# HH-08MX.net
KiCad netlist of a schematic drawn in EAGLE
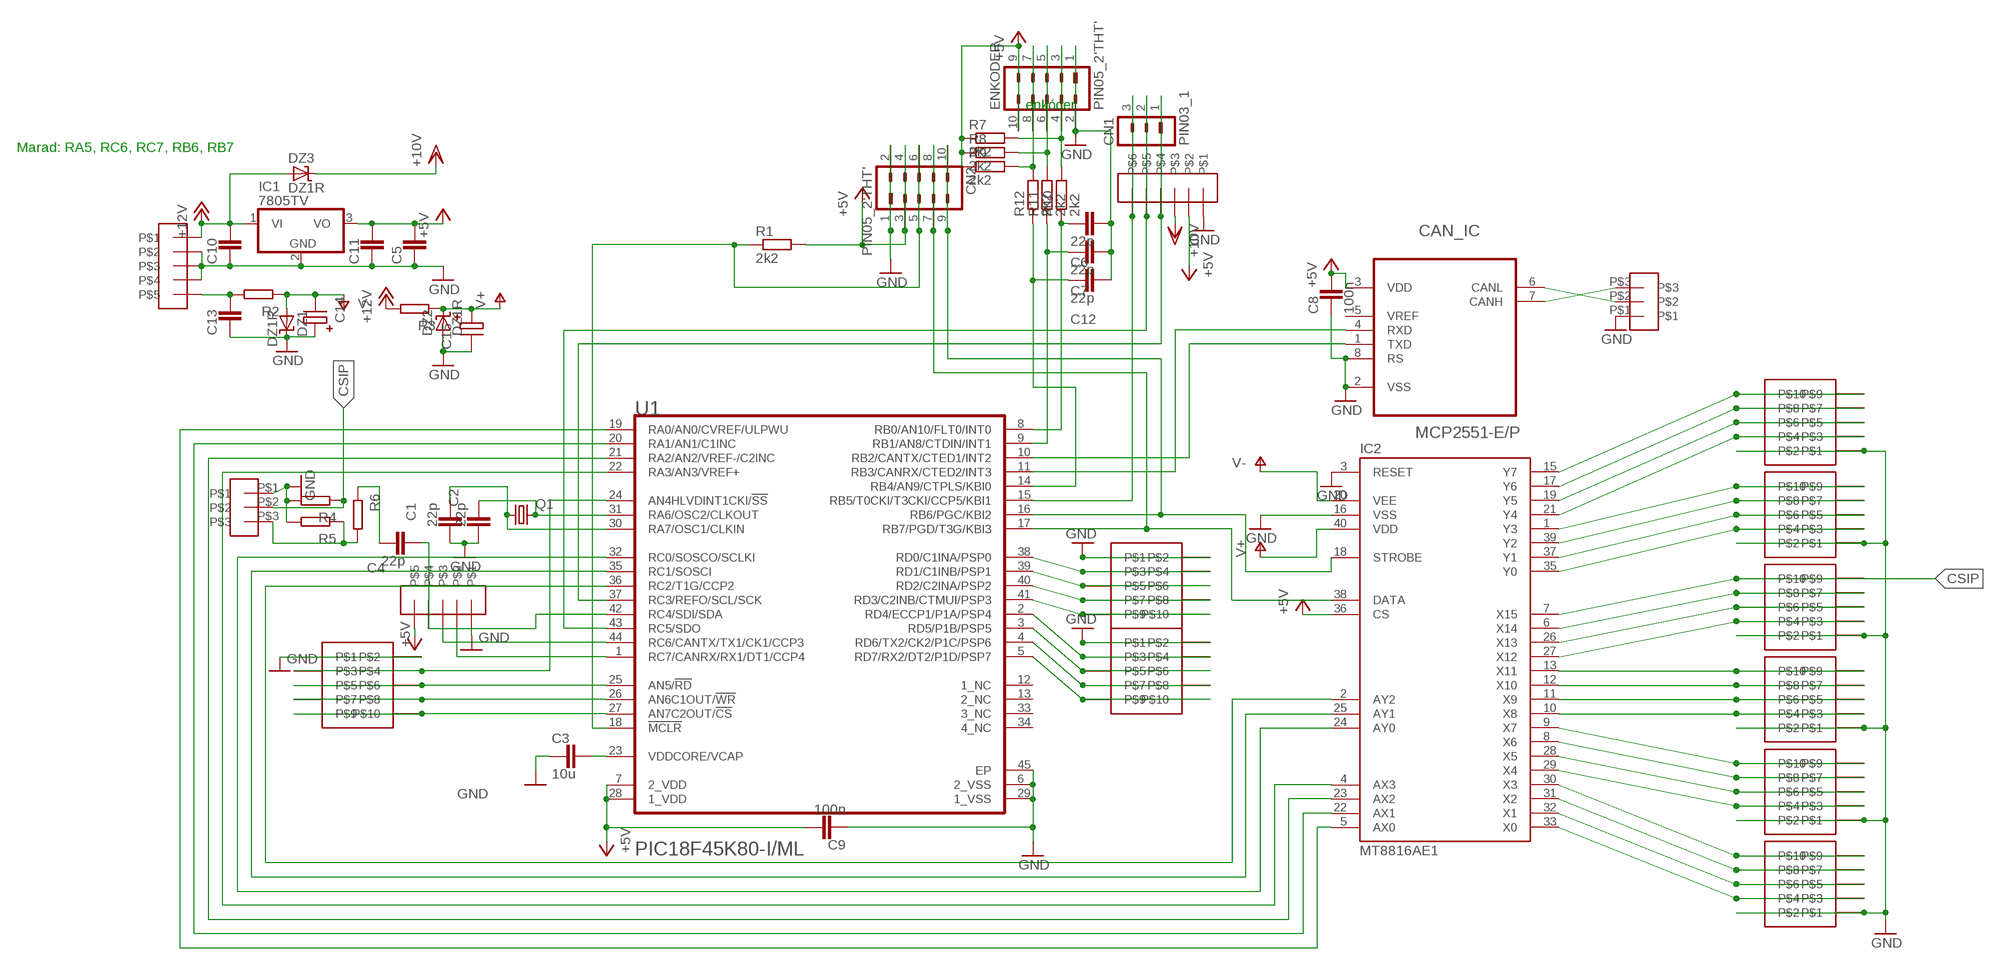
[diagram p0: schematic, sheet 1]

(export (version "E")
  (design (tool "Eeschema 10.0.6"))
  (components
    (comp (ref "BE1-4")
      (value "KERETES_TUS_10")
      (footprint "eagle-import:KERETES_TUS_10")
      (libsource (lib "eagle-import") (part "KERETES_TUS_10"))
    )
    (comp (ref "BE5-8")
      (value "KERETES_TUS_10")
      (footprint "eagle-import:KERETES_TUS_10")
      (libsource (lib "eagle-import") (part "KERETES_TUS_10"))
    )
    (comp (ref "BE9-12")
      (value "KERETES_TUS_10")
      (footprint "eagle-import:KERETES_TUS_10")
      (libsource (lib "eagle-import") (part "KERETES_TUS_10"))
    )
    (comp (ref "BE13-16")
      (value "KERETES_TUS_10")
      (footprint "eagle-import:KERETES_TUS_10")
      (libsource (lib "eagle-import") (part "KERETES_TUS_10"))
    )
    (comp (ref "C1")
      (value "22p")
      (footprint "eagle-import:R_0805_NAGY")
      (libsource (lib "eagle-import") (part "C0805_NAGY"))
    )
    (comp (ref "C2")
      (value "22p")
      (footprint "eagle-import:R_0805_NAGY")
      (libsource (lib "eagle-import") (part "C0805_NAGY"))
    )
    (comp (ref "C3")
      (value "10u")
      (footprint "eagle-import:R_0805_NAGY")
      (libsource (lib "eagle-import") (part "C0805_NAGY"))
    )
    (comp (ref "C4")
      (value "22p")
      (footprint "eagle-import:R_0805_NAGY")
      (libsource (lib "eagle-import") (part "C0805_NAGY"))
    )
    (comp (ref "C5")
      (value "C0805_NAGY")
      (footprint "eagle-import:R_0805_NAGY")
      (libsource (lib "eagle-import") (part "C0805_NAGY"))
    )
    (comp (ref "C6")
      (value "22p")
      (footprint "eagle-import:R_0805_NAGY")
      (libsource (lib "eagle-import") (part "C0805_NAGY"))
    )
    (comp (ref "C7")
      (value "22p")
      (footprint "eagle-import:R_0805_NAGY")
      (libsource (lib "eagle-import") (part "C0805_NAGY"))
    )
    (comp (ref "C8")
      (value "100n")
      (footprint "eagle-import:R_0805_NAGY")
      (libsource (lib "eagle-import") (part "C0805_NAGY"))
    )
    (comp (ref "C9")
      (value "100n")
      (footprint "eagle-import:R_0805_NAGY")
      (libsource (lib "eagle-import") (part "C0805_NAGY"))
    )
    (comp (ref "C10")
      (value "C0805_NAGY")
      (footprint "eagle-import:R_0805_NAGY")
      (libsource (lib "eagle-import") (part "C0805_NAGY"))
    )
    (comp (ref "C11")
      (value "C0805_NAGY")
      (footprint "eagle-import:R_0805_NAGY")
      (libsource (lib "eagle-import") (part "C0805_NAGY"))
    )
    (comp (ref "C12")
      (value "22p")
      (footprint "eagle-import:R_0805_NAGY")
      (libsource (lib "eagle-import") (part "C0805_NAGY"))
    )
    (comp (ref "C13")
      (value "C0805_NAGY")
      (footprint "eagle-import:R_0805_NAGY")
      (libsource (lib "eagle-import") (part "C0805_NAGY"))
    )
    (comp (ref "C14")
      (value "C_EL1R06")
      (footprint "eagle-import:C_EL1RASZT06")
      (libsource (lib "eagle-import") (part "C_EL1R06"))
    )
    (comp (ref "C15")
      (value "C_EL1R06")
      (footprint "eagle-import:C_EL1RASZT06")
      (libsource (lib "eagle-import") (part "C_EL1R06"))
    )
    (comp (ref "CAN_IC")
      (value "MCP2551-E/P")
      (footprint "eagle-import:DIP254P762X432-8")
      (libsource (lib "eagle-import") (part "MCP2551-E/P"))
    )
    (comp (ref "CN1")
      (value "PIN03_1")
      (footprint "eagle-import:PIN03_1")
      (libsource (lib "eagle-import") (part "PIN03_1"))
    )
    (comp (ref "CN2")
      (value "PIN05_2'THT'")
      (footprint "eagle-import:PIN05_2")
      (libsource (lib "eagle-import") (part "PIN05_2'THT'"))
    )
    (comp (ref "DZ1")
      (value "DZ1R")
      (footprint "eagle-import:D1RASZT")
      (libsource (lib "eagle-import") (part "DZ1R"))
    )
    (comp (ref "DZ2")
      (value "DZ1R")
      (footprint "eagle-import:D1RASZT")
      (libsource (lib "eagle-import") (part "DZ1R"))
    )
    (comp (ref "DZ3")
      (value "DZ1R")
      (footprint "eagle-import:D1RASZT")
      (libsource (lib "eagle-import") (part "DZ1R"))
    )
    (comp (ref "ENKODER")
      (value "PIN05_2'THT'")
      (footprint "eagle-import:PIN05_2")
      (libsource (lib "eagle-import") (part "PIN05_2'THT'"))
    )
    (comp (ref "IC1")
      (value "7805TV")
      (footprint "eagle-import:TO220V")
      (libsource (lib "eagle-import") (part "78TV05"))
    )
    (comp (ref "IC2")
      (value "MT8816AE1")
      (footprint "eagle-import:DIL40")
      (libsource (lib "eagle-import") (part "MT8816AE1"))
    )
    (comp (ref "KI1-4")
      (value "KERETES_TUS_10")
      (footprint "eagle-import:KERETES_TUS_10")
      (libsource (lib "eagle-import") (part "KERETES_TUS_10"))
    )
    (comp (ref "KI5-8")
      (value "KERETES_TUS_10")
      (footprint "eagle-import:KERETES_TUS_10")
      (libsource (lib "eagle-import") (part "KERETES_TUS_10"))
    )
    (comp (ref "KIJELZO")
      (value "FEHER_TUS_6")
      (footprint "eagle-import:FEHER_TUS_6")
      (libsource (lib "eagle-import") (part "FEHER_TUS_6"))
    )
    (comp (ref "Q1")
      (value "XTAL_2QS")
      (footprint "eagle-import:XTAL_QS")
      (libsource (lib "eagle-import") (part "XTAL_2QS"))
    )
    (comp (ref "R1")
      (value "2k2")
      (footprint "eagle-import:R0805")
      (libsource (lib "eagle-import") (part "R-EU_R0805"))
    )
    (comp (ref "R2")
      (value "R_EU0805_NAGY")
      (footprint "eagle-import:R_0805_NAGY")
      (libsource (lib "eagle-import") (part "R_EU0805_NAGY"))
    )
    (comp (ref "R3")
      (value "R_EU0805_NAGY")
      (footprint "eagle-import:R_0805_NAGY")
      (libsource (lib "eagle-import") (part "R_EU0805_NAGY"))
    )
    (comp (ref "R4")
      (value "R_EU0805_NAGY")
      (footprint "eagle-import:R_0805_NAGY")
      (libsource (lib "eagle-import") (part "R_EU0805_NAGY"))
    )
    (comp (ref "R5")
      (value "R_EU0805_NAGY")
      (footprint "eagle-import:R_0805_NAGY")
      (libsource (lib "eagle-import") (part "R_EU0805_NAGY"))
    )
    (comp (ref "R6")
      (value "R_EU0805_NAGY")
      (footprint "eagle-import:R_0805_NAGY")
      (libsource (lib "eagle-import") (part "R_EU0805_NAGY"))
    )
    (comp (ref "R7")
      (value "2k2")
      (footprint "eagle-import:R0805")
      (libsource (lib "eagle-import") (part "R-EU_R0805"))
    )
    (comp (ref "R8")
      (value "2k2")
      (footprint "eagle-import:R0805")
      (libsource (lib "eagle-import") (part "R-EU_R0805"))
    )
    (comp (ref "R9")
      (value "2k2")
      (footprint "eagle-import:R0805")
      (libsource (lib "eagle-import") (part "R-EU_R0805"))
    )
    (comp (ref "R10")
      (value "2k2")
      (footprint "eagle-import:R0805")
      (libsource (lib "eagle-import") (part "R-EU_R0805"))
    )
    (comp (ref "R11")
      (value "2k2")
      (footprint "eagle-import:R0805")
      (libsource (lib "eagle-import") (part "R-EU_R0805"))
    )
    (comp (ref "R12")
      (value "2k2")
      (footprint "eagle-import:R0805")
      (libsource (lib "eagle-import") (part "R-EU_R0805"))
    )
    (comp (ref "SOROSPORT")
      (value "FEHER_TUS_5")
      (footprint "eagle-import:FEHER_TUS_5")
      (libsource (lib "eagle-import") (part "FEHER_TUS_5"))
    )
    (comp (ref "U$1")
      (value "FEHER_TUS_3")
      (footprint "eagle-import:FEHER_TUS_3")
      (libsource (lib "eagle-import") (part "FEHER_TUS_3"))
    )
    (comp (ref "U$4")
      (value "FEHER_TUS_3")
      (footprint "eagle-import:FEHER_TUS_3")
      (libsource (lib "eagle-import") (part "FEHER_TUS_3"))
    )
    (comp (ref "U$5")
      (value "FEHER_TUS_5")
      (footprint "eagle-import:FEHER_TUS_5")
      (libsource (lib "eagle-import") (part "FEHER_TUS_5"))
    )
    (comp (ref "U$14")
      (value "KERETES_TUS_10")
      (footprint "eagle-import:KERETES_TUS_10")
      (libsource (lib "eagle-import") (part "KERETES_TUS_10"))
    )
    (comp (ref "U$15")
      (value "KERETES_TUS_10")
      (footprint "eagle-import:KERETES_TUS_10")
      (libsource (lib "eagle-import") (part "KERETES_TUS_10"))
    )
    (comp (ref "U$16")
      (value "KERETES_TUS_10")
      (footprint "eagle-import:KERETES_TUS_10")
      (libsource (lib "eagle-import") (part "KERETES_TUS_10"))
    )
    (comp (ref "U1")
      (value "MICROCHIP_PIC18F45K80-I-MLMICROCHIP_PIC18F45K80-I-ML_0_2")
      (footprint "eagle-import:MICROCHIP_PIC18F45K80-I-ML_2")
      (fields (field (name "MF") "Microchip") (field (name "MPN") "PIC18F45K80-I/ML"))
      (libsource (lib "eagle-import") (part "MICROCHIP_PIC18F45K80-I-MLMICROCHIP_PIC18F45K80-I-ML_0_2"))
    )
  )
  (nets
    (net (code "1") (name "+5V") (class "Default")
      (node (ref "C11") (pin "1") (pinfunction "1_1") (pintype "passive"))
      (node (ref "C5") (pin "1") (pinfunction "1_1") (pintype "passive"))
      (node (ref "C8") (pin "1") (pinfunction "1_1") (pintype "passive"))
      (node (ref "C9") (pin "1") (pinfunction "1_1") (pintype "passive"))
      (node (ref "CAN_IC") (pin "3") (pinfunction "VDD_3") (pintype "power_in"))
      (node (ref "CN2") (pin "3") (pinfunction "3_3") (pintype "passive"))
      (node (ref "CN2") (pin "4") (pinfunction "4_4") (pintype "passive"))
      (node (ref "ENKODER") (pin "10") (pinfunction "10_10") (pintype "passive"))
      (node (ref "ENKODER") (pin "9") (pinfunction "9_9") (pintype "passive"))
      (node (ref "IC1") (pin "3") (pinfunction "VO_3") (pintype "passive"))
      (node (ref "IC2") (pin "36") (pinfunction "CS_36") (pintype "input"))
      (node (ref "KIJELZO") (pin "P$2") (pinfunction "P$2_P$2") (pintype "bidirectional"))
      (node (ref "R1") (pin "2") (pinfunction "2_2") (pintype "passive"))
      (node (ref "R7") (pin "1") (pinfunction "1_1") (pintype "passive"))
      (node (ref "R8") (pin "1") (pinfunction "1_1") (pintype "passive"))
      (node (ref "R9") (pin "1") (pinfunction "1_1") (pintype "passive"))
      (node (ref "SOROSPORT") (pin "P$5") (pinfunction "P$5_P$5") (pintype "bidirectional"))
      (node (ref "U1") (pin "28") (pinfunction "1_VDD_28") (pintype "power_in"))
      (node (ref "U1") (pin "7") (pinfunction "2_VDD_7") (pintype "power_in"))
    )
    (net (code "2") (name "+10V") (class "Default")
      (node (ref "DZ3") (pin "P$2") (pinfunction "C_P$2") (pintype "passive"))
      (node (ref "KIJELZO") (pin "P$3") (pinfunction "P$3_P$3") (pintype "bidirectional"))
    )
    (net (code "3") (name "+12V") (class "Default")
      (node (ref "C10") (pin "1") (pinfunction "1_1") (pintype "passive"))
      (node (ref "DZ3") (pin "P$1") (pinfunction "A_P$1") (pintype "passive"))
      (node (ref "IC1") (pin "1") (pinfunction "VI_1") (pintype "input"))
      (node (ref "R3") (pin "2") (pinfunction "E_2") (pintype "passive"))
      (node (ref "U$5") (pin "P$1") (pinfunction "P$1_P$1") (pintype "bidirectional"))
    )
    (net (code "4") (name "CSIP") (class "Default")
      (node (ref "BE13-16") (pin "P$10") (pinfunction "P$10_P$10") (pintype "bidirectional"))
      (node (ref "BE13-16") (pin "P$9") (pinfunction "P$9_P$9") (pintype "bidirectional"))
      (node (ref "IC2") (pin "7") (pinfunction "X15_7") (pintype "bidirectional"))
      (node (ref "R4") (pin "1") (pinfunction "A_1") (pintype "passive"))
      (node (ref "U$1") (pin "P$2") (pinfunction "P$2_P$2") (pintype "bidirectional"))
    )
    (net (code "5") (name "GND") (class "Default")
      (node (ref "BE1-4") (pin "P$1") (pinfunction "P$1_P$1") (pintype "bidirectional"))
      (node (ref "BE1-4") (pin "P$2") (pinfunction "P$2_P$2") (pintype "bidirectional"))
      (node (ref "BE13-16") (pin "P$1") (pinfunction "P$1_P$1") (pintype "bidirectional"))
      (node (ref "BE13-16") (pin "P$2") (pinfunction "P$2_P$2") (pintype "bidirectional"))
      (node (ref "BE5-8") (pin "P$1") (pinfunction "P$1_P$1") (pintype "bidirectional"))
      (node (ref "BE5-8") (pin "P$2") (pinfunction "P$2_P$2") (pintype "bidirectional"))
      (node (ref "BE9-12") (pin "P$1") (pinfunction "P$1_P$1") (pintype "bidirectional"))
      (node (ref "BE9-12") (pin "P$2") (pinfunction "P$2_P$2") (pintype "bidirectional"))
      (node (ref "C1") (pin "1") (pinfunction "1_1") (pintype "passive"))
      (node (ref "C10") (pin "2") (pinfunction "2_2") (pintype "passive"))
      (node (ref "C11") (pin "2") (pinfunction "2_2") (pintype "passive"))
      (node (ref "C12") (pin "1") (pinfunction "1_1") (pintype "passive"))
      (node (ref "C13") (pin "2") (pinfunction "2_2") (pintype "passive"))
      (node (ref "C14") (pin "P+") (pinfunction "P+_P+") (pintype "passive"))
      (node (ref "C15") (pin "P-") (pinfunction "P-_P-") (pintype "passive"))
      (node (ref "C2") (pin "1") (pinfunction "1_1") (pintype "passive"))
      (node (ref "C3") (pin "2") (pinfunction "2_2") (pintype "passive"))
      (node (ref "C5") (pin "2") (pinfunction "2_2") (pintype "passive"))
      (node (ref "C6") (pin "1") (pinfunction "1_1") (pintype "passive"))
      (node (ref "C7") (pin "1") (pinfunction "1_1") (pintype "passive"))
      (node (ref "C8") (pin "2") (pinfunction "2_2") (pintype "passive"))
      (node (ref "C9") (pin "2") (pinfunction "2_2") (pintype "passive"))
      (node (ref "CAN_IC") (pin "2") (pinfunction "VSS_2") (pintype "passive"))
      (node (ref "CAN_IC") (pin "8") (pinfunction "RS_8") (pintype "input"))
      (node (ref "CN2") (pin "1") (pinfunction "1_1") (pintype "passive"))
      (node (ref "CN2") (pin "2") (pinfunction "2_2") (pintype "passive"))
      (node (ref "DZ1") (pin "P$2") (pinfunction "C_P$2") (pintype "passive"))
      (node (ref "DZ2") (pin "P$1") (pinfunction "A_P$1") (pintype "passive"))
      (node (ref "ENKODER") (pin "1") (pinfunction "1_1") (pintype "passive"))
      (node (ref "ENKODER") (pin "2") (pinfunction "2_2") (pintype "passive"))
      (node (ref "IC1") (pin "2") (pinfunction "GND_2") (pintype "passive"))
      (node (ref "IC2") (pin "16") (pinfunction "VSS_16") (pintype "power_in"))
      (node (ref "IC2") (pin "3") (pinfunction "RESET_3") (pintype "input"))
      (node (ref "KI1-4") (pin "P$1") (pinfunction "P$1_P$1") (pintype "bidirectional"))
      (node (ref "KI1-4") (pin "P$2") (pinfunction "P$2_P$2") (pintype "bidirectional"))
      (node (ref "KI5-8") (pin "P$1") (pinfunction "P$1_P$1") (pintype "bidirectional"))
      (node (ref "KI5-8") (pin "P$2") (pinfunction "P$2_P$2") (pintype "bidirectional"))
      (node (ref "KIJELZO") (pin "P$1") (pinfunction "P$1_P$1") (pintype "bidirectional"))
      (node (ref "R4") (pin "2") (pinfunction "E_2") (pintype "passive"))
      (node (ref "R5") (pin "2") (pinfunction "E_2") (pintype "passive"))
      (node (ref "SOROSPORT") (pin "P$1") (pinfunction "P$1_P$1") (pintype "bidirectional"))
      (node (ref "U$1") (pin "P$1") (pinfunction "P$1_P$1") (pintype "bidirectional"))
      (node (ref "U$14") (pin "P$1") (pinfunction "P$1_P$1") (pintype "bidirectional"))
      (node (ref "U$14") (pin "P$2") (pinfunction "P$2_P$2") (pintype "bidirectional"))
      (node (ref "U$15") (pin "P$1") (pinfunction "P$1_P$1") (pintype "bidirectional"))
      (node (ref "U$15") (pin "P$2") (pinfunction "P$2_P$2") (pintype "bidirectional"))
      (node (ref "U$16") (pin "P$1") (pinfunction "P$1_P$1") (pintype "bidirectional"))
      (node (ref "U$16") (pin "P$2") (pinfunction "P$2_P$2") (pintype "bidirectional"))
      (node (ref "U$4") (pin "P$1") (pinfunction "P$1_P$1") (pintype "bidirectional"))
      (node (ref "U$5") (pin "P$2") (pinfunction "P$2_P$2") (pintype "bidirectional"))
      (node (ref "U$5") (pin "P$3") (pinfunction "P$3_P$3") (pintype "bidirectional"))
      (node (ref "U$5") (pin "P$4") (pinfunction "P$4_P$4") (pintype "bidirectional"))
      (node (ref "U1") (pin "29") (pinfunction "1_VSS_29") (pintype "power_in"))
      (node (ref "U1") (pin "45") (pinfunction "EP_45") (pintype "power_in"))
      (node (ref "U1") (pin "6") (pinfunction "2_VSS_6") (pintype "power_in"))
    )
    (net (code "6") (name "Net-(CAN_IC-CANH)") (class "Default")
      (node (ref "CAN_IC") (pin "7") (pinfunction "CANH_7") (pintype "output"))
      (node (ref "U$4") (pin "P$3") (pinfunction "P$3_P$3") (pintype "bidirectional"))
    )
    (net (code "7") (name "Net-(CAN_IC-CANL)") (class "Default")
      (node (ref "CAN_IC") (pin "6") (pinfunction "CANL_6") (pintype "output"))
      (node (ref "U$4") (pin "P$2") (pinfunction "P$2_P$2") (pintype "bidirectional"))
    )
    (net (code "8") (name "Net-(CAN_IC-RXD)") (class "Default")
      (node (ref "CAN_IC") (pin "4") (pinfunction "RXD_4") (pintype "input"))
      (node (ref "U1") (pin "11") (pinfunction "RB3/CANRX/CTED2/INT3_11") (pintype "bidirectional"))
    )
    (net (code "9") (name "Net-(CAN_IC-TXD)") (class "Default")
      (node (ref "CAN_IC") (pin "1") (pinfunction "TXD_1") (pintype "input"))
      (node (ref "U1") (pin "10") (pinfunction "RB2/CANTX/CTED1/INT2_10") (pintype "bidirectional"))
    )
    (net (code "10") (name "Net-(ENKODER-Pad3)") (class "Default")
      (node (ref "ENKODER") (pin "3") (pinfunction "3_3") (pintype "passive"))
      (node (ref "ENKODER") (pin "4") (pinfunction "4_4") (pintype "passive"))
      (node (ref "R10") (pin "2") (pinfunction "2_2") (pintype "passive"))
      (node (ref "R7") (pin "2") (pinfunction "2_2") (pintype "passive"))
    )
    (net (code "11") (name "Net-(ENKODER-Pad5)") (class "Default")
      (node (ref "ENKODER") (pin "5") (pinfunction "5_5") (pintype "passive"))
      (node (ref "ENKODER") (pin "6") (pinfunction "6_6") (pintype "passive"))
      (node (ref "R11") (pin "2") (pinfunction "2_2") (pintype "passive"))
      (node (ref "R8") (pin "2") (pinfunction "2_2") (pintype "passive"))
    )
    (net (code "12") (name "Net-(ENKODER-Pad7)") (class "Default")
      (node (ref "ENKODER") (pin "7") (pinfunction "7_7") (pintype "passive"))
      (node (ref "ENKODER") (pin "8") (pinfunction "8_8") (pintype "passive"))
      (node (ref "R12") (pin "2") (pinfunction "2_2") (pintype "passive"))
      (node (ref "R9") (pin "2") (pinfunction "2_2") (pintype "passive"))
    )
    (net (code "13") (name "Net-(IC2-AX0)") (class "Default")
      (node (ref "IC2") (pin "5") (pinfunction "AX0_5") (pintype "input"))
      (node (ref "U1") (pin "19") (pinfunction "RA0/AN0/CVREF/ULPWU_19") (pintype "bidirectional"))
    )
    (net (code "14") (name "Net-(IC2-AX1)") (class "Default")
      (node (ref "IC2") (pin "22") (pinfunction "AX1_22") (pintype "input"))
      (node (ref "U1") (pin "20") (pinfunction "RA1/AN1/C1INC_20") (pintype "bidirectional"))
    )
    (net (code "15") (name "Net-(IC2-AX2)") (class "Default")
      (node (ref "IC2") (pin "23") (pinfunction "AX2_23") (pintype "input"))
      (node (ref "U1") (pin "21") (pinfunction "RA2/AN2/VREF-/C2INC_21") (pintype "bidirectional"))
    )
    (net (code "16") (name "Net-(IC2-AX3)") (class "Default")
      (node (ref "IC2") (pin "4") (pinfunction "AX3_4") (pintype "input"))
      (node (ref "U1") (pin "22") (pinfunction "RA3/AN3/VREF+_22") (pintype "bidirectional"))
    )
    (net (code "17") (name "Net-(IC2-AY0)") (class "Default")
      (node (ref "IC2") (pin "24") (pinfunction "AY0_24") (pintype "input"))
      (node (ref "U1") (pin "32") (pinfunction "RC0/SOSCO/SCLKI_32") (pintype "bidirectional"))
    )
    (net (code "18") (name "Net-(IC2-AY1)") (class "Default")
      (node (ref "IC2") (pin "25") (pinfunction "AY1_25") (pintype "input"))
      (node (ref "U1") (pin "35") (pinfunction "RC1/SOSCI_35") (pintype "bidirectional"))
    )
    (net (code "19") (name "Net-(IC2-AY2)") (class "Default")
      (node (ref "IC2") (pin "2") (pinfunction "AY2_2") (pintype "input"))
      (node (ref "U1") (pin "36") (pinfunction "RC2/T1G/CCP2_36") (pintype "bidirectional"))
    )
    (net (code "20") (name "Net-(IC2-DATA)") (class "Default")
      (node (ref "CN2") (pin "7") (pinfunction "7_7") (pintype "passive"))
      (node (ref "CN2") (pin "8") (pinfunction "8_8") (pintype "passive"))
      (node (ref "IC2") (pin "38") (pinfunction "DATA_38") (pintype "input"))
      (node (ref "U1") (pin "17") (pinfunction "RB7/PGD/T3G/KBI3_17") (pintype "bidirectional"))
    )
    (net (code "21") (name "Net-(IC2-STROBE)") (class "Default")
      (node (ref "CN2") (pin "10") (pinfunction "10_10") (pintype "passive"))
      (node (ref "CN2") (pin "9") (pinfunction "9_9") (pintype "passive"))
      (node (ref "IC2") (pin "18") (pinfunction "STROBE_18") (pintype "input"))
      (node (ref "U1") (pin "16") (pinfunction "RB6/PGC/KBI2_16") (pintype "bidirectional"))
    )
    (net (code "22") (name "Net-(IC2-X0)") (class "Default")
      (node (ref "BE1-4") (pin "P$3") (pinfunction "P$3_P$3") (pintype "bidirectional"))
      (node (ref "BE1-4") (pin "P$4") (pinfunction "P$4_P$4") (pintype "bidirectional"))
      (node (ref "IC2") (pin "33") (pinfunction "X0_33") (pintype "bidirectional"))
    )
    (net (code "23") (name "Net-(IC2-X1)") (class "Default")
      (node (ref "BE1-4") (pin "P$5") (pinfunction "P$5_P$5") (pintype "bidirectional"))
      (node (ref "BE1-4") (pin "P$6") (pinfunction "P$6_P$6") (pintype "bidirectional"))
      (node (ref "IC2") (pin "32") (pinfunction "X1_32") (pintype "bidirectional"))
    )
    (net (code "24") (name "Net-(IC2-X2)") (class "Default")
      (node (ref "BE1-4") (pin "P$7") (pinfunction "P$7_P$7") (pintype "bidirectional"))
      (node (ref "BE1-4") (pin "P$8") (pinfunction "P$8_P$8") (pintype "bidirectional"))
      (node (ref "IC2") (pin "31") (pinfunction "X2_31") (pintype "bidirectional"))
    )
    (net (code "25") (name "Net-(IC2-X3)") (class "Default")
      (node (ref "BE1-4") (pin "P$10") (pinfunction "P$10_P$10") (pintype "bidirectional"))
      (node (ref "BE1-4") (pin "P$9") (pinfunction "P$9_P$9") (pintype "bidirectional"))
      (node (ref "IC2") (pin "30") (pinfunction "X3_30") (pintype "bidirectional"))
    )
    (net (code "26") (name "Net-(IC2-X4)") (class "Default")
      (node (ref "BE5-8") (pin "P$3") (pinfunction "P$3_P$3") (pintype "bidirectional"))
      (node (ref "BE5-8") (pin "P$4") (pinfunction "P$4_P$4") (pintype "bidirectional"))
      (node (ref "IC2") (pin "29") (pinfunction "X4_29") (pintype "bidirectional"))
    )
    (net (code "27") (name "Net-(IC2-X5)") (class "Default")
      (node (ref "BE5-8") (pin "P$5") (pinfunction "P$5_P$5") (pintype "bidirectional"))
      (node (ref "BE5-8") (pin "P$6") (pinfunction "P$6_P$6") (pintype "bidirectional"))
      (node (ref "IC2") (pin "28") (pinfunction "X5_28") (pintype "bidirectional"))
    )
    (net (code "28") (name "Net-(IC2-X6)") (class "Default")
      (node (ref "BE5-8") (pin "P$7") (pinfunction "P$7_P$7") (pintype "bidirectional"))
      (node (ref "BE5-8") (pin "P$8") (pinfunction "P$8_P$8") (pintype "bidirectional"))
      (node (ref "IC2") (pin "8") (pinfunction "X6_8") (pintype "bidirectional"))
    )
    (net (code "29") (name "Net-(IC2-X7)") (class "Default")
      (node (ref "BE5-8") (pin "P$10") (pinfunction "P$10_P$10") (pintype "bidirectional"))
      (node (ref "BE5-8") (pin "P$9") (pinfunction "P$9_P$9") (pintype "bidirectional"))
      (node (ref "IC2") (pin "9") (pinfunction "X7_9") (pintype "bidirectional"))
    )
    (net (code "30") (name "Net-(IC2-X8)") (class "Default")
      (node (ref "BE9-12") (pin "P$3") (pinfunction "P$3_P$3") (pintype "bidirectional"))
      (node (ref "BE9-12") (pin "P$4") (pinfunction "P$4_P$4") (pintype "bidirectional"))
      (node (ref "IC2") (pin "10") (pinfunction "X8_10") (pintype "bidirectional"))
    )
    (net (code "31") (name "Net-(IC2-X9)") (class "Default")
      (node (ref "BE9-12") (pin "P$5") (pinfunction "P$5_P$5") (pintype "bidirectional"))
      (node (ref "BE9-12") (pin "P$6") (pinfunction "P$6_P$6") (pintype "bidirectional"))
      (node (ref "IC2") (pin "11") (pinfunction "X9_11") (pintype "bidirectional"))
    )
    (net (code "32") (name "Net-(IC2-X10)") (class "Default")
      (node (ref "BE9-12") (pin "P$7") (pinfunction "P$7_P$7") (pintype "bidirectional"))
      (node (ref "BE9-12") (pin "P$8") (pinfunction "P$8_P$8") (pintype "bidirectional"))
      (node (ref "IC2") (pin "12") (pinfunction "X10_12") (pintype "bidirectional"))
    )
    (net (code "33") (name "Net-(IC2-X11)") (class "Default")
      (node (ref "BE9-12") (pin "P$10") (pinfunction "P$10_P$10") (pintype "bidirectional"))
      (node (ref "BE9-12") (pin "P$9") (pinfunction "P$9_P$9") (pintype "bidirectional"))
      (node (ref "IC2") (pin "13") (pinfunction "X11_13") (pintype "bidirectional"))
    )
    (net (code "34") (name "Net-(IC2-X12)") (class "Default")
      (node (ref "BE13-16") (pin "P$3") (pinfunction "P$3_P$3") (pintype "bidirectional"))
      (node (ref "BE13-16") (pin "P$4") (pinfunction "P$4_P$4") (pintype "bidirectional"))
      (node (ref "IC2") (pin "27") (pinfunction "X12_27") (pintype "bidirectional"))
    )
    (net (code "35") (name "Net-(IC2-X13)") (class "Default")
      (node (ref "BE13-16") (pin "P$5") (pinfunction "P$5_P$5") (pintype "bidirectional"))
      (node (ref "BE13-16") (pin "P$6") (pinfunction "P$6_P$6") (pintype "bidirectional"))
      (node (ref "IC2") (pin "26") (pinfunction "X13_26") (pintype "bidirectional"))
    )
    (net (code "36") (name "Net-(IC2-X14)") (class "Default")
      (node (ref "BE13-16") (pin "P$7") (pinfunction "P$7_P$7") (pintype "bidirectional"))
      (node (ref "BE13-16") (pin "P$8") (pinfunction "P$8_P$8") (pintype "bidirectional"))
      (node (ref "IC2") (pin "6") (pinfunction "X14_6") (pintype "bidirectional"))
    )
    (net (code "37") (name "Net-(IC2-Y0)") (class "Default")
      (node (ref "IC2") (pin "35") (pinfunction "Y0_35") (pintype "bidirectional"))
      (node (ref "KI1-4") (pin "P$3") (pinfunction "P$3_P$3") (pintype "bidirectional"))
      (node (ref "KI1-4") (pin "P$4") (pinfunction "P$4_P$4") (pintype "bidirectional"))
    )
    (net (code "38") (name "Net-(IC2-Y1)") (class "Default")
      (node (ref "IC2") (pin "37") (pinfunction "Y1_37") (pintype "bidirectional"))
      (node (ref "KI1-4") (pin "P$5") (pinfunction "P$5_P$5") (pintype "bidirectional"))
      (node (ref "KI1-4") (pin "P$6") (pinfunction "P$6_P$6") (pintype "bidirectional"))
    )
    (net (code "39") (name "Net-(IC2-Y2)") (class "Default")
      (node (ref "IC2") (pin "39") (pinfunction "Y2_39") (pintype "bidirectional"))
      (node (ref "KI1-4") (pin "P$7") (pinfunction "P$7_P$7") (pintype "bidirectional"))
      (node (ref "KI1-4") (pin "P$8") (pinfunction "P$8_P$8") (pintype "bidirectional"))
    )
    (net (code "40") (name "Net-(IC2-Y3)") (class "Default")
      (node (ref "IC2") (pin "1") (pinfunction "Y3_1") (pintype "bidirectional"))
      (node (ref "KI1-4") (pin "P$10") (pinfunction "P$10_P$10") (pintype "bidirectional"))
      (node (ref "KI1-4") (pin "P$9") (pinfunction "P$9_P$9") (pintype "bidirectional"))
    )
    (net (code "41") (name "Net-(IC2-Y4)") (class "Default")
      (node (ref "IC2") (pin "21") (pinfunction "Y4_21") (pintype "bidirectional"))
      (node (ref "KI5-8") (pin "P$3") (pinfunction "P$3_P$3") (pintype "bidirectional"))
      (node (ref "KI5-8") (pin "P$4") (pinfunction "P$4_P$4") (pintype "bidirectional"))
    )
    (net (code "42") (name "Net-(IC2-Y5)") (class "Default")
      (node (ref "IC2") (pin "19") (pinfunction "Y5_19") (pintype "bidirectional"))
      (node (ref "KI5-8") (pin "P$5") (pinfunction "P$5_P$5") (pintype "bidirectional"))
      (node (ref "KI5-8") (pin "P$6") (pinfunction "P$6_P$6") (pintype "bidirectional"))
    )
    (net (code "43") (name "Net-(IC2-Y6)") (class "Default")
      (node (ref "IC2") (pin "17") (pinfunction "Y6_17") (pintype "bidirectional"))
      (node (ref "KI5-8") (pin "P$7") (pinfunction "P$7_P$7") (pintype "bidirectional"))
      (node (ref "KI5-8") (pin "P$8") (pinfunction "P$8_P$8") (pintype "bidirectional"))
    )
    (net (code "44") (name "Net-(IC2-Y7)") (class "Default")
      (node (ref "IC2") (pin "15") (pinfunction "Y7_15") (pintype "bidirectional"))
      (node (ref "KI5-8") (pin "P$10") (pinfunction "P$10_P$10") (pintype "bidirectional"))
      (node (ref "KI5-8") (pin "P$9") (pinfunction "P$9_P$9") (pintype "bidirectional"))
    )
    (net (code "45") (name "Net-(R2-E)") (class "Default")
      (node (ref "C13") (pin "1") (pinfunction "1_1") (pintype "passive"))
      (node (ref "R2") (pin "2") (pinfunction "E_2") (pintype "passive"))
      (node (ref "U$5") (pin "P$5") (pinfunction "P$5_P$5") (pintype "bidirectional"))
    )
    (net (code "46") (name "Net-(R5-A)") (class "Default")
      (node (ref "R5") (pin "1") (pinfunction "A_1") (pintype "passive"))
      (node (ref "R6") (pin "2") (pinfunction "E_2") (pintype "passive"))
      (node (ref "U$1") (pin "P$3") (pinfunction "P$3_P$3") (pintype "bidirectional"))
    )
    (net (code "47") (name "Net-(R6-A)") (class "Default")
      (node (ref "C4") (pin "2") (pinfunction "2_2") (pintype "passive"))
      (node (ref "R6") (pin "1") (pinfunction "A_1") (pintype "passive"))
    )
    (net (code "48") (name "Net-(U1-AN4HLVDINT1CKI{slash}~{SS})") (class "Default")
      (node (ref "U$16") (pin "P$3") (pinfunction "P$3_P$3") (pintype "bidirectional"))
      (node (ref "U$16") (pin "P$4") (pinfunction "P$4_P$4") (pintype "bidirectional"))
      (node (ref "U1") (pin "24") (pinfunction "AN4HLVDINT1CKI/~{SS}_24") (pintype "bidirectional"))
    )
    (net (code "49") (name "Net-(U1-AN5{slash}~{RD})") (class "Default")
      (node (ref "U$16") (pin "P$5") (pinfunction "P$5_P$5") (pintype "bidirectional"))
      (node (ref "U$16") (pin "P$6") (pinfunction "P$6_P$6") (pintype "bidirectional"))
      (node (ref "U1") (pin "25") (pinfunction "AN5/~{RD}_25") (pintype "bidirectional"))
    )
    (net (code "50") (name "Net-(U1-AN6C1OUT{slash}~{WR})") (class "Default")
      (node (ref "U$16") (pin "P$7") (pinfunction "P$7_P$7") (pintype "bidirectional"))
      (node (ref "U$16") (pin "P$8") (pinfunction "P$8_P$8") (pintype "bidirectional"))
      (node (ref "U1") (pin "26") (pinfunction "AN6C1OUT/~{WR}_26") (pintype "bidirectional"))
    )
    (net (code "51") (name "Net-(U1-AN7C2OUT{slash}~{CS})") (class "Default")
      (node (ref "U$16") (pin "P$10") (pinfunction "P$10_P$10") (pintype "bidirectional"))
      (node (ref "U$16") (pin "P$9") (pinfunction "P$9_P$9") (pintype "bidirectional"))
      (node (ref "U1") (pin "27") (pinfunction "AN7C2OUT/~{CS}_27") (pintype "bidirectional"))
    )
    (net (code "52") (name "Net-(U1-RA6{slash}OSC2{slash}CLKOUT)") (class "Default")
      (node (ref "C2") (pin "2") (pinfunction "2_2") (pintype "passive"))
      (node (ref "Q1") (pin "2") (pinfunction "2_2") (pintype "passive"))
      (node (ref "U1") (pin "31") (pinfunction "RA6/OSC2/CLKOUT_31") (pintype "bidirectional"))
    )
    (net (code "53") (name "Net-(U1-RA7{slash}OSC1{slash}CLKIN)") (class "Default")
      (node (ref "C1") (pin "2") (pinfunction "2_2") (pintype "passive"))
      (node (ref "Q1") (pin "1") (pinfunction "1_1") (pintype "passive"))
      (node (ref "U1") (pin "30") (pinfunction "RA7/OSC1/CLKIN_30") (pintype "bidirectional"))
    )
    (net (code "54") (name "Net-(U1-RB0{slash}AN10{slash}FLT0{slash}INT0)") (class "Default")
      (node (ref "C6") (pin "2") (pinfunction "2_2") (pintype "passive"))
      (node (ref "R10") (pin "1") (pinfunction "1_1") (pintype "passive"))
      (node (ref "U1") (pin "8") (pinfunction "RB0/AN10/FLT0/INT0_8") (pintype "bidirectional"))
    )
    (net (code "55") (name "Net-(U1-RB1{slash}AN8{slash}CTDIN{slash}INT1)") (class "Default")
      (node (ref "C7") (pin "2") (pinfunction "2_2") (pintype "passive"))
      (node (ref "R11") (pin "1") (pinfunction "1_1") (pintype "passive"))
      (node (ref "U1") (pin "9") (pinfunction "RB1/AN8/CTDIN/INT1_9") (pintype "bidirectional"))
    )
    (net (code "56") (name "Net-(U1-RB4{slash}AN9{slash}CTPLS{slash}KBI0)") (class "Default")
      (node (ref "C12") (pin "2") (pinfunction "2_2") (pintype "passive"))
      (node (ref "R12") (pin "1") (pinfunction "1_1") (pintype "passive"))
      (node (ref "U1") (pin "14") (pinfunction "RB4/AN9/CTPLS/KBI0_14") (pintype "bidirectional"))
    )
    (net (code "57") (name "Net-(U1-RB5{slash}T0CKI{slash}T3CKI{slash}CCP5{slash}KBI1)") (class "Default")
      (node (ref "CN1") (pin "3") (pinfunction "3_3") (pintype "passive"))
      (node (ref "KIJELZO") (pin "P$6") (pinfunction "P$6_P$6") (pintype "bidirectional"))
      (node (ref "U1") (pin "15") (pinfunction "RB5/T0CKI/T3CKI/CCP5/KBI1_15") (pintype "bidirectional"))
    )
    (net (code "58") (name "Net-(U1-RC3{slash}REFO{slash}SCL{slash}SCK)") (class "Default")
      (node (ref "CN1") (pin "1") (pinfunction "1_1") (pintype "passive"))
      (node (ref "KIJELZO") (pin "P$4") (pinfunction "P$4_P$4") (pintype "bidirectional"))
      (node (ref "U1") (pin "37") (pinfunction "RC3/REFO/SCL/SCK_37") (pintype "bidirectional"))
    )
    (net (code "59") (name "Net-(U1-RC4{slash}SDI{slash}SDA)") (class "Default")
      (node (ref "C4") (pin "1") (pinfunction "1_1") (pintype "passive"))
      (node (ref "SOROSPORT") (pin "P$4") (pinfunction "P$4_P$4") (pintype "bidirectional"))
      (node (ref "U1") (pin "42") (pinfunction "RC4/SDI/SDA_42") (pintype "bidirectional"))
    )
    (net (code "60") (name "Net-(U1-RC5{slash}SDO)") (class "Default")
      (node (ref "CN1") (pin "2") (pinfunction "2_2") (pintype "passive"))
      (node (ref "KIJELZO") (pin "P$5") (pinfunction "P$5_P$5") (pintype "bidirectional"))
      (node (ref "U1") (pin "43") (pinfunction "RC5/SDO_43") (pintype "bidirectional"))
    )
    (net (code "61") (name "Net-(U1-RC6{slash}CANTX{slash}TX1{slash}CK1{slash}CCP3)") (class "Default")
      (node (ref "SOROSPORT") (pin "P$3") (pinfunction "P$3_P$3") (pintype "bidirectional"))
      (node (ref "U1") (pin "44") (pinfunction "RC6/CANTX/TX1/CK1/CCP3_44") (pintype "bidirectional"))
    )
    (net (code "62") (name "Net-(U1-RC7{slash}CANRX{slash}RX1{slash}DT1{slash}CCP4)") (class "Default")
      (node (ref "SOROSPORT") (pin "P$2") (pinfunction "P$2_P$2") (pintype "bidirectional"))
      (node (ref "U1") (pin "1") (pinfunction "RC7/CANRX/RX1/DT1/CCP4_1") (pintype "bidirectional"))
    )
    (net (code "63") (name "Net-(U1-RD0{slash}C1INA{slash}PSP0)") (class "Default")
      (node (ref "U$14") (pin "P$3") (pinfunction "P$3_P$3") (pintype "bidirectional"))
      (node (ref "U$14") (pin "P$4") (pinfunction "P$4_P$4") (pintype "bidirectional"))
      (node (ref "U1") (pin "38") (pinfunction "RD0/C1INA/PSP0_38") (pintype "bidirectional"))
    )
    (net (code "64") (name "Net-(U1-RD1{slash}C1INB{slash}PSP1)") (class "Default")
      (node (ref "U$14") (pin "P$5") (pinfunction "P$5_P$5") (pintype "bidirectional"))
      (node (ref "U$14") (pin "P$6") (pinfunction "P$6_P$6") (pintype "bidirectional"))
      (node (ref "U1") (pin "39") (pinfunction "RD1/C1INB/PSP1_39") (pintype "bidirectional"))
    )
    (net (code "65") (name "Net-(U1-RD2{slash}C2INA{slash}PSP2)") (class "Default")
      (node (ref "U$14") (pin "P$7") (pinfunction "P$7_P$7") (pintype "bidirectional"))
      (node (ref "U$14") (pin "P$8") (pinfunction "P$8_P$8") (pintype "bidirectional"))
      (node (ref "U1") (pin "40") (pinfunction "RD2/C2INA/PSP2_40") (pintype "bidirectional"))
    )
    (net (code "66") (name "Net-(U1-RD3{slash}C2INB{slash}CTMUI{slash}PSP3)") (class "Default")
      (node (ref "U$14") (pin "P$10") (pinfunction "P$10_P$10") (pintype "bidirectional"))
      (node (ref "U$14") (pin "P$9") (pinfunction "P$9_P$9") (pintype "bidirectional"))
      (node (ref "U1") (pin "41") (pinfunction "RD3/C2INB/CTMUI/PSP3_41") (pintype "bidirectional"))
    )
    (net (code "67") (name "Net-(U1-RD4{slash}ECCP1{slash}P1A{slash}PSP4)") (class "Default")
      (node (ref "U$15") (pin "P$3") (pinfunction "P$3_P$3") (pintype "bidirectional"))
      (node (ref "U$15") (pin "P$4") (pinfunction "P$4_P$4") (pintype "bidirectional"))
      (node (ref "U1") (pin "2") (pinfunction "RD4/ECCP1/P1A/PSP4_2") (pintype "bidirectional"))
    )
    (net (code "68") (name "Net-(U1-RD5{slash}P1B{slash}PSP5)") (class "Default")
      (node (ref "U$15") (pin "P$5") (pinfunction "P$5_P$5") (pintype "bidirectional"))
      (node (ref "U$15") (pin "P$6") (pinfunction "P$6_P$6") (pintype "bidirectional"))
      (node (ref "U1") (pin "3") (pinfunction "RD5/P1B/PSP5_3") (pintype "bidirectional"))
    )
    (net (code "69") (name "Net-(U1-RD6{slash}TX2{slash}CK2{slash}P1C{slash}PSP6)") (class "Default")
      (node (ref "U$15") (pin "P$7") (pinfunction "P$7_P$7") (pintype "bidirectional"))
      (node (ref "U$15") (pin "P$8") (pinfunction "P$8_P$8") (pintype "bidirectional"))
      (node (ref "U1") (pin "4") (pinfunction "RD6/TX2/CK2/P1C/PSP6_4") (pintype "bidirectional"))
    )
    (net (code "70") (name "Net-(U1-RD7{slash}RX2{slash}DT2{slash}P1D{slash}PSP7)") (class "Default")
      (node (ref "U$15") (pin "P$10") (pinfunction "P$10_P$10") (pintype "bidirectional"))
      (node (ref "U$15") (pin "P$9") (pinfunction "P$9_P$9") (pintype "bidirectional"))
      (node (ref "U1") (pin "5") (pinfunction "RD7/RX2/DT2/P1D/PSP7_5") (pintype "bidirectional"))
    )
    (net (code "71") (name "Net-(U1-VDDCORE{slash}VCAP)") (class "Default")
      (node (ref "C3") (pin "1") (pinfunction "1_1") (pintype "passive"))
      (node (ref "U1") (pin "23") (pinfunction "VDDCORE/VCAP_23") (pintype "power_in"))
    )
    (net (code "72") (name "Net-(U1-~{MCLR})") (class "Default")
      (node (ref "CN2") (pin "5") (pinfunction "5_5") (pintype "passive"))
      (node (ref "CN2") (pin "6") (pinfunction "6_6") (pintype "passive"))
      (node (ref "R1") (pin "1") (pinfunction "1_1") (pintype "passive"))
      (node (ref "U1") (pin "18") (pinfunction "~{MCLR}_18") (pintype "input"))
    )
    (net (code "73") (name "V+") (class "Default")
      (node (ref "C15") (pin "P+") (pinfunction "P+_P+") (pintype "passive"))
      (node (ref "DZ2") (pin "P$2") (pinfunction "C_P$2") (pintype "passive"))
      (node (ref "IC2") (pin "40") (pinfunction "VDD_40") (pintype "power_in"))
      (node (ref "R3") (pin "1") (pinfunction "A_1") (pintype "passive"))
    )
    (net (code "74") (name "V-") (class "Default")
      (node (ref "C14") (pin "P-") (pinfunction "P-_P-") (pintype "passive"))
      (node (ref "DZ1") (pin "P$1") (pinfunction "A_P$1") (pintype "passive"))
      (node (ref "IC2") (pin "20") (pinfunction "VEE_20") (pintype "power_in"))
      (node (ref "R2") (pin "1") (pinfunction "A_1") (pintype "passive"))
    )
    (net (code "75") (name "unconnected-(CAN_IC-VREF-Pad5)") (class "Default")
      (node (ref "CAN_IC") (pin "5") (pinfunction "VREF_5") (pintype "input"))
    )
    (net (code "76") (name "unconnected-(U1-1_NC-Pad12)") (class "Default")
      (node (ref "U1") (pin "12") (pinfunction "1_NC_12") (pintype "passive"))
    )
    (net (code "77") (name "unconnected-(U1-2_NC-Pad13)") (class "Default")
      (node (ref "U1") (pin "13") (pinfunction "2_NC_13") (pintype "passive"))
    )
    (net (code "78") (name "unconnected-(U1-3_NC-Pad33)") (class "Default")
      (node (ref "U1") (pin "33") (pinfunction "3_NC_33") (pintype "passive"))
    )
    (net (code "79") (name "unconnected-(U1-4_NC-Pad34)") (class "Default")
      (node (ref "U1") (pin "34") (pinfunction "4_NC_34") (pintype "passive"))
    )
  )
)
